# TC_switch_to_shield_connection.net
KiCad netlist of a schematic drawn in Altium Designer
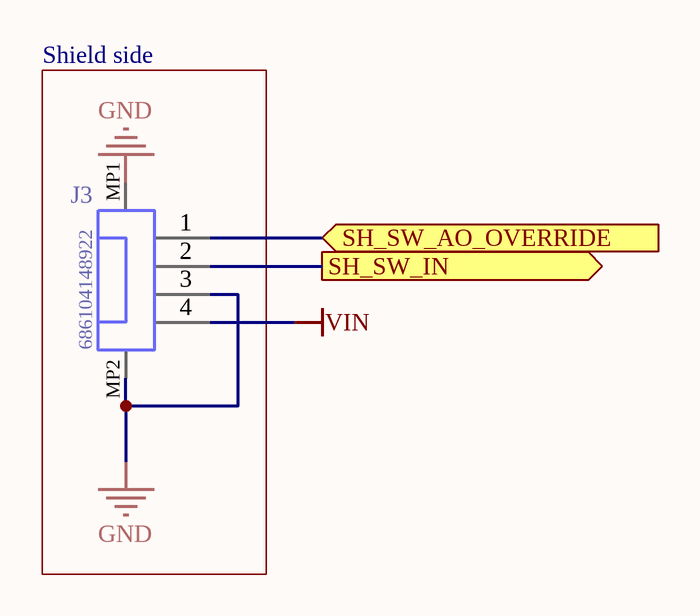
[diagram p0: TC_switch_to_shield_connection.SchDoc]

(export (version "E")
  (design (tool "Eeschema 10.0.6"))
  (components
    (comp (ref "J3")
      (value "686104148922")
      (footprint "686104148922")
      (description "SMT ZIF Connectors Hinge Type WR-FPC, Horizontal, Bottom Contact, pitch 1 mm, 4 pins")
      (fields (field (name "MANUFACTURER") "Wurth Elektronik") (field (name "PUBLISHER") "WurthElektronik"))
      (libsource (lib "Altium Content Vault") (part "WE-6861041XXX22-4"))
    )
  )
  (nets
    (net (code "1") (name "/SH_SW_AO_OVERRIDE") (class "Default")
      (node (ref "J3") (pin "1") (pinfunction "1_1") (pintype "passive"))
    )
    (net (code "2") (name "/SH_SW_IN") (class "Default")
      (node (ref "J3") (pin "2") (pinfunction "2_2") (pintype "passive"))
    )
    (net (code "3") (name "GND") (class "Default")
      (node (ref "J3") (pin "3") (pinfunction "3_3") (pintype "passive"))
      (node (ref "J3") (pin "MP1") (pinfunction "MP1_MP1") (pintype "passive"))
      (node (ref "J3") (pin "MP2") (pinfunction "MP2_MP2") (pintype "passive"))
    )
    (net (code "4") (name "VIN") (class "Default")
      (node (ref "J3") (pin "4") (pinfunction "4_4") (pintype "passive"))
    )
  )
)
